# lipo.net
KiCad netlist of a schematic drawn in EAGLE
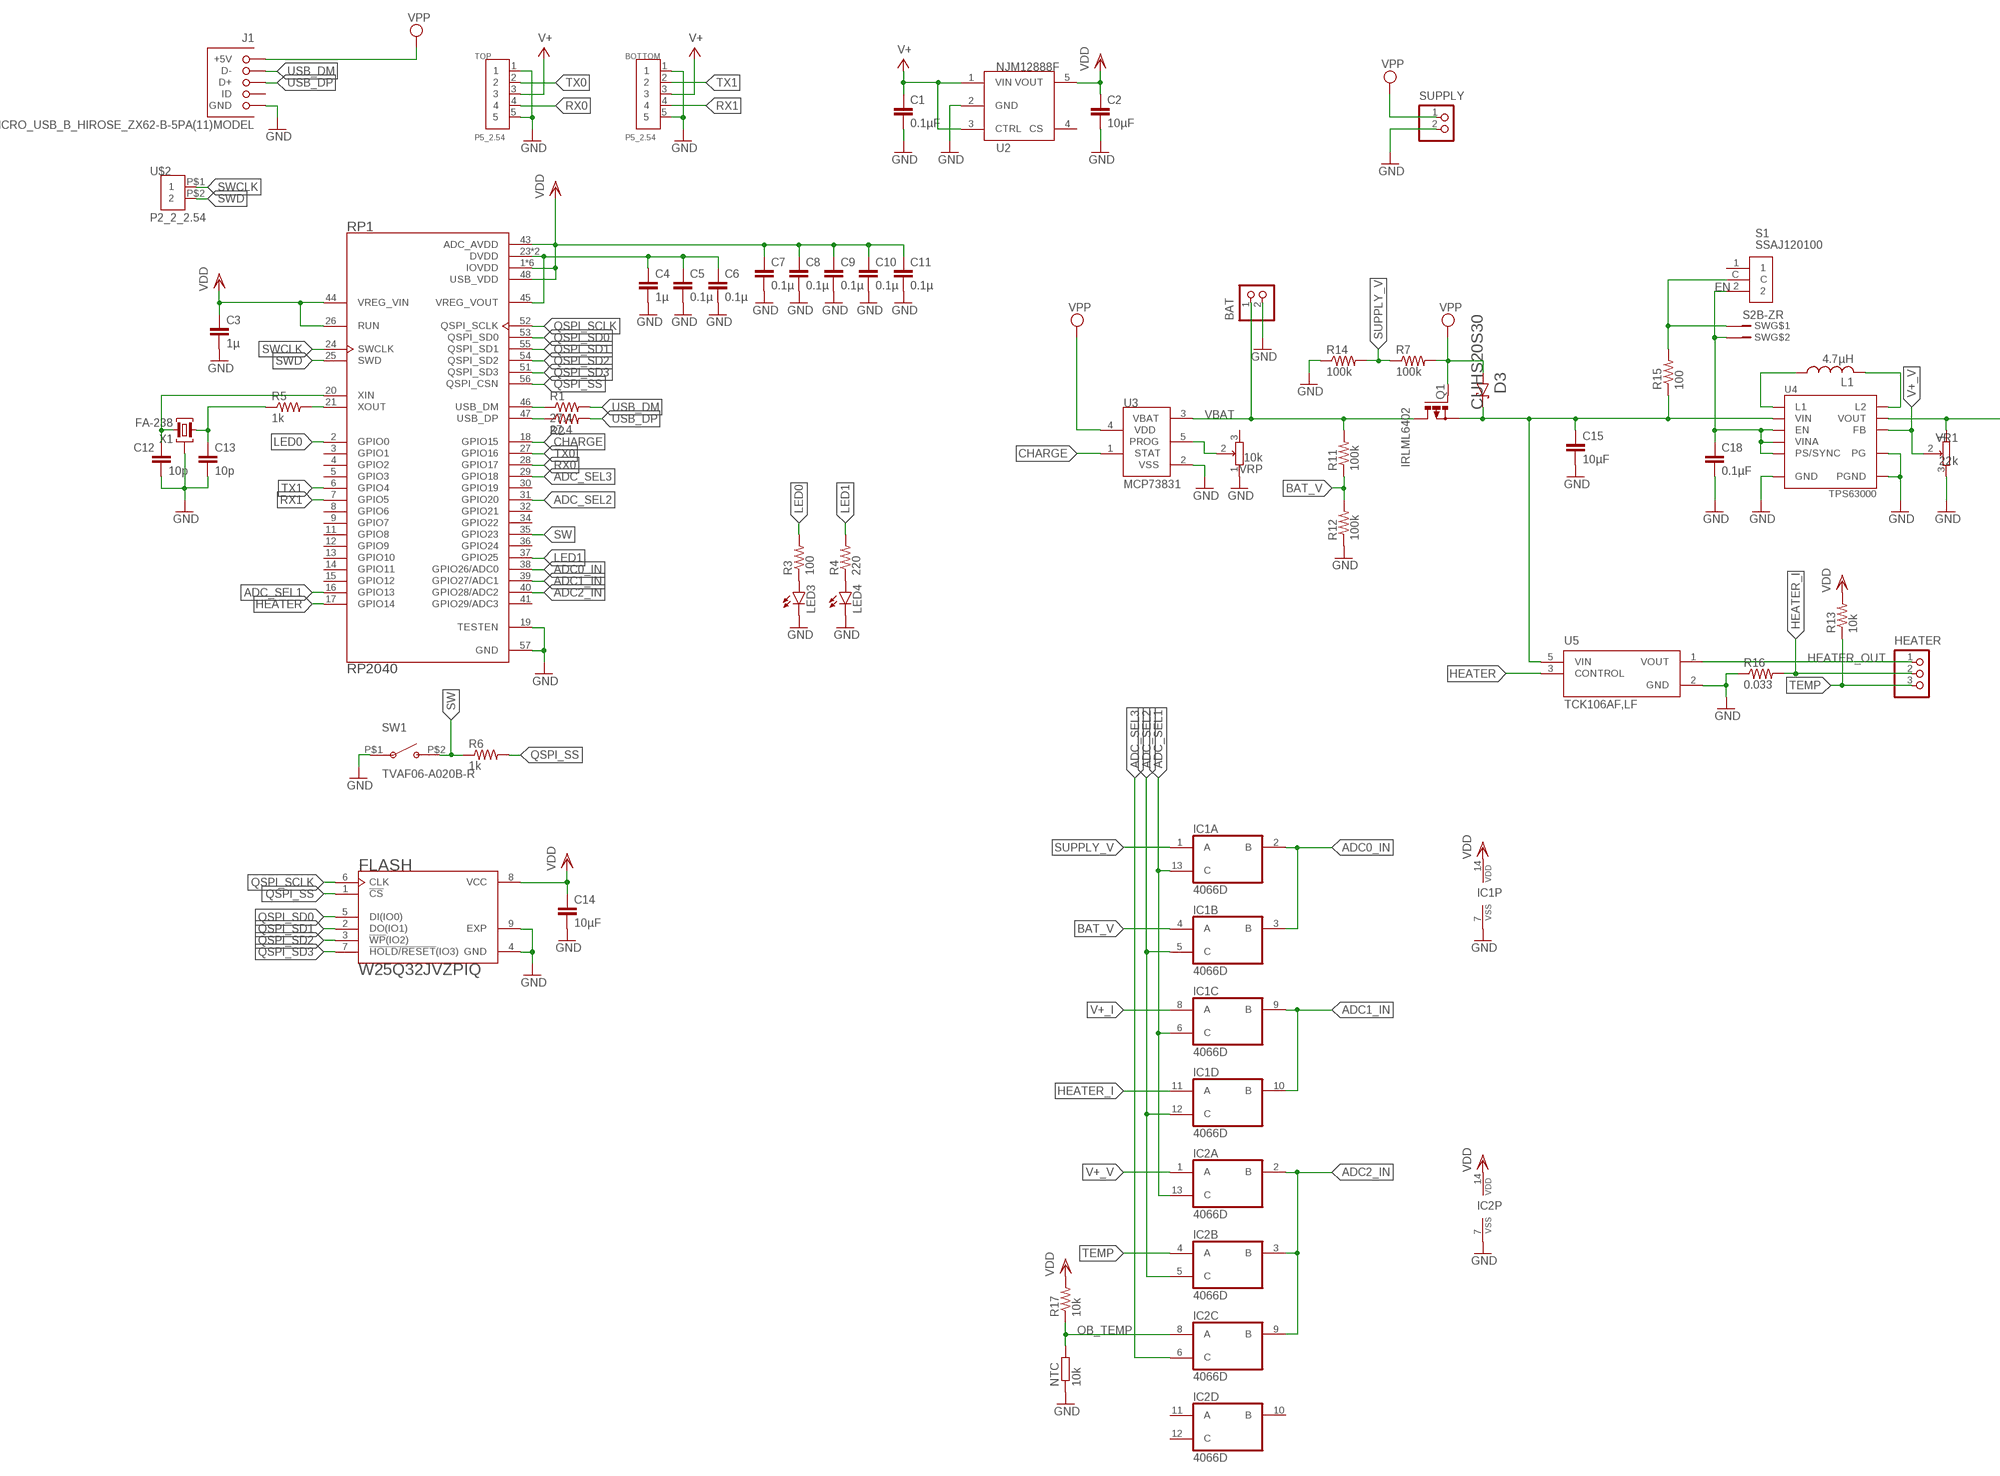
[diagram p0: schematic, sheet 1, part 1 of 2]
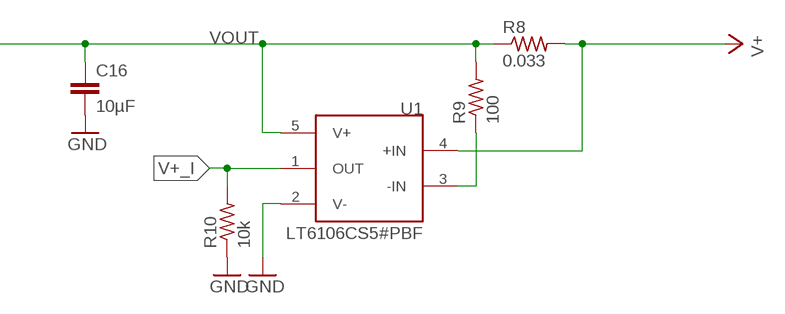
[diagram p1: schematic, sheet 1, part 2 of 2]

(export (version "E")
  (design (tool "Eeschema 10.0.6"))
  (components
    (comp (ref "BAT")
      (value "S2B-PH-K-S")
      (footprint "eagle-import:S2B-PH-K-S")
      (libsource (lib "eagle-import") (part "S2B-PH-K-S"))
    )
    (comp (ref "BOTTOM")
      (value "P5_2.54")
      (footprint "eagle-import:P5_2.54")
      (libsource (lib "eagle-import") (part "P5_2.54"))
    )
    (comp (ref "C1")
      (value "0.1µF")
      (footprint "eagle-import:C0402")
      (libsource (lib "eagle-import") (part "C-EUC0402"))
    )
    (comp (ref "C2")
      (value "10µF")
      (footprint "eagle-import:C0402")
      (libsource (lib "eagle-import") (part "C-EUC0402"))
    )
    (comp (ref "C3")
      (value "1µ")
      (footprint "eagle-import:C0402")
      (libsource (lib "eagle-import") (part "C-EUC0402"))
    )
    (comp (ref "C4")
      (value "1µ")
      (footprint "eagle-import:C0402")
      (libsource (lib "eagle-import") (part "C-EUC0402"))
    )
    (comp (ref "C5")
      (value "0.1µ")
      (footprint "eagle-import:C0402")
      (libsource (lib "eagle-import") (part "C-EUC0402"))
    )
    (comp (ref "C6")
      (value "0.1µ")
      (footprint "eagle-import:C0402")
      (libsource (lib "eagle-import") (part "C-EUC0402"))
    )
    (comp (ref "C7")
      (value "0.1µ")
      (footprint "eagle-import:C0402")
      (libsource (lib "eagle-import") (part "C-EUC0402"))
    )
    (comp (ref "C8")
      (value "0.1µ")
      (footprint "eagle-import:C0402")
      (libsource (lib "eagle-import") (part "C-EUC0402"))
    )
    (comp (ref "C9")
      (value "0.1µ")
      (footprint "eagle-import:C0402")
      (libsource (lib "eagle-import") (part "C-EUC0402"))
    )
    (comp (ref "C10")
      (value "0.1µ")
      (footprint "eagle-import:C0402")
      (libsource (lib "eagle-import") (part "C-EUC0402"))
    )
    (comp (ref "C11")
      (value "0.1µ")
      (footprint "eagle-import:C0402")
      (libsource (lib "eagle-import") (part "C-EUC0402"))
    )
    (comp (ref "C12")
      (value "10p")
      (footprint "eagle-import:C0402")
      (libsource (lib "eagle-import") (part "C-EUC0402"))
    )
    (comp (ref "C13")
      (value "10p")
      (footprint "eagle-import:C0402")
      (libsource (lib "eagle-import") (part "C-EUC0402"))
    )
    (comp (ref "C14")
      (value "10µF")
      (footprint "eagle-import:C0402")
      (libsource (lib "eagle-import") (part "C-EUC0402"))
    )
    (comp (ref "C15")
      (value "10µF")
      (footprint "eagle-import:C0402")
      (libsource (lib "eagle-import") (part "C-EUC0402"))
    )
    (comp (ref "C16")
      (value "10µF")
      (footprint "eagle-import:C0402")
      (libsource (lib "eagle-import") (part "C-EUC0402"))
    )
    (comp (ref "C18")
      (value "0.1µF")
      (footprint "eagle-import:C0402")
      (libsource (lib "eagle-import") (part "C-EUC0402"))
    )
    (comp (ref "D3")
      (value "CUHS20S30")
      (footprint "eagle-import:CUHS20S30")
      (libsource (lib "eagle-import") (part "CUHS20S30"))
    )
    (comp (ref "FLASH")
      (value "W25Q32JVZPIQ")
      (footprint "eagle-import:SON127P600X500X80-9N")
      (fields (field (name "MF") "Winbond"))
      (libsource (lib "eagle-import") (part "W25Q32JVZPIQ"))
    )
    (comp (ref "HEATER")
      (value "S3B-PH-K-S")
      (footprint "eagle-import:S3B-PH-K-S")
      (libsource (lib "eagle-import") (part "S3B-PH-K-S"))
    )
    (comp (ref "IC1")
      (value "4066D")
      (footprint "eagle-import:SO14")
      (libsource (lib "eagle-import") (part "4066D"))
    )
    (comp (ref "IC2")
      (value "4066D")
      (footprint "eagle-import:SO14")
      (libsource (lib "eagle-import") (part "4066D"))
    )
    (comp (ref "J1")
      (value "MICRO_USB_B_HIROSE_ZX62-B-5PA(11)MODEL")
      (footprint "eagle-import:GHI-CONNECTORS_10118192-0001LF(MICRO-USB-B-AMPHENOL-FCI)")
      (libsource (lib "eagle-import") (part "MICRO_USB_B_HIROSE_ZX62-B-5PA(11)MODEL"))
    )
    (comp (ref "L1")
      (value "4.7µH")
      (footprint "eagle-import:L3225M")
      (libsource (lib "eagle-import") (part "L-USL3225M"))
    )
    (comp (ref "LED3")
      (value "LEDCHIPLED_0603")
      (footprint "eagle-import:CHIPLED_0603")
      (libsource (lib "eagle-import") (part "LEDCHIPLED_0603"))
    )
    (comp (ref "LED4")
      (value "LEDCHIPLED_0603")
      (footprint "eagle-import:CHIPLED_0603")
      (libsource (lib "eagle-import") (part "LEDCHIPLED_0603"))
    )
    (comp (ref "NTC")
      (value "10k")
      (footprint "eagle-import:R0603")
      (libsource (lib "eagle-import") (part "R-EU_R0603"))
    )
    (comp (ref "Q1")
      (value "IRLML6402")
      (footprint "eagle-import:SOT-23")
      (libsource (lib "eagle-import") (part "IRLML6402"))
    )
    (comp (ref "R1")
      (value "27.4")
      (footprint "eagle-import:R0402")
      (libsource (lib "eagle-import") (part "R-US_R0402"))
    )
    (comp (ref "R2")
      (value "27.4")
      (footprint "eagle-import:R0402")
      (libsource (lib "eagle-import") (part "R-US_R0402"))
    )
    (comp (ref "R3")
      (value "100")
      (footprint "eagle-import:R0402")
      (libsource (lib "eagle-import") (part "R-US_R0402"))
    )
    (comp (ref "R4")
      (value "220")
      (footprint "eagle-import:R0402")
      (libsource (lib "eagle-import") (part "R-US_R0402"))
    )
    (comp (ref "R5")
      (value "1k")
      (footprint "eagle-import:R0402")
      (libsource (lib "eagle-import") (part "R-US_R0402"))
    )
    (comp (ref "R6")
      (value "1k")
      (footprint "eagle-import:R0402")
      (libsource (lib "eagle-import") (part "R-US_R0402"))
    )
    (comp (ref "R7")
      (value "100k")
      (footprint "eagle-import:R0402")
      (libsource (lib "eagle-import") (part "R-US_R0402"))
    )
    (comp (ref "R8")
      (value "0.033")
      (footprint "eagle-import:R0603")
      (libsource (lib "eagle-import") (part "R-US_R0603"))
    )
    (comp (ref "R9")
      (value "100")
      (footprint "eagle-import:R0402")
      (libsource (lib "eagle-import") (part "R-US_R0402"))
    )
    (comp (ref "R10")
      (value "10k")
      (footprint "eagle-import:R0402")
      (libsource (lib "eagle-import") (part "R-US_R0402"))
    )
    (comp (ref "R11")
      (value "100k")
      (footprint "eagle-import:R0402")
      (libsource (lib "eagle-import") (part "R-US_R0402"))
    )
    (comp (ref "R12")
      (value "100k")
      (footprint "eagle-import:R0402")
      (libsource (lib "eagle-import") (part "R-US_R0402"))
    )
    (comp (ref "R13")
      (value "10k")
      (footprint "eagle-import:R0402")
      (libsource (lib "eagle-import") (part "R-US_R0402"))
    )
    (comp (ref "R14")
      (value "100k")
      (footprint "eagle-import:R0402")
      (libsource (lib "eagle-import") (part "R-US_R0402"))
    )
    (comp (ref "R15")
      (value "100")
      (footprint "eagle-import:R0402")
      (libsource (lib "eagle-import") (part "R-US_R0402"))
    )
    (comp (ref "R16")
      (value "0.033")
      (footprint "eagle-import:R0603")
      (libsource (lib "eagle-import") (part "R-US_R0603"))
    )
    (comp (ref "R17")
      (value "10k")
      (footprint "eagle-import:R0402")
      (libsource (lib "eagle-import") (part "R-US_R0402"))
    )
    (comp (ref "RP1")
      (value "RP2040")
      (footprint "eagle-import:QFN40P700X700X90-57N")
      (fields (field (name "MF") "Raspberry Pi"))
      (libsource (lib "eagle-import") (part "RP2040"))
    )
    (comp (ref "S1")
      (value "SSAJ120100")
      (footprint "eagle-import:SSAJ120100")
      (fields (field (name "MOUSER_PART_NUMBER") "688-SSAJ120100") (field (name "RS_PART_NUMBER") "1238892"))
      (libsource (lib "eagle-import") (part "SSAJ120100"))
    )
    (comp (ref "SUPPLY")
      (value "S2B-PH-K-S")
      (footprint "eagle-import:S2B-PH-K-S")
      (libsource (lib "eagle-import") (part "S2B-PH-K-S"))
    )
    (comp (ref "SW")
      (value "S2B-ZR")
      (footprint "eagle-import:S2B-ZR")
      (libsource (lib "eagle-import") (part "S2B-ZR"))
    )
    (comp (ref "SW1")
      (value "TVAF06-A020B-R")
      (footprint "eagle-import:TVAF06-A020B-R")
      (libsource (lib "eagle-import") (part "TVAF06-A020B-R"))
    )
    (comp (ref "TOP")
      (value "P5_2.54")
      (footprint "eagle-import:P5_2.54")
      (libsource (lib "eagle-import") (part "P5_2.54"))
    )
    (comp (ref "U$2")
      (value "P2_2_2.54")
      (footprint "eagle-import:P2_2.54")
      (libsource (lib "eagle-import") (part "P2_2_2.54"))
    )
    (comp (ref "U1")
      (value "LT6106CS5#PBF")
      (footprint "eagle-import:SOT95P280X100-5N_LT6106CS5#PBF")
      (fields (field (name "MF") "Linear Technology"))
      (libsource (lib "eagle-import") (part "LT6106CS5#PBF"))
    )
    (comp (ref "U2")
      (value "NJM12888F")
      (footprint "eagle-import:SOT95P240X110-5N")
      (libsource (lib "eagle-import") (part "NJM12888F"))
    )
    (comp (ref "U3")
      (value "MCP73831")
      (footprint "eagle-import:SOT23-5L")
      (libsource (lib "eagle-import") (part "MCP73831"))
    )
    (comp (ref "U4")
      (value "TPS63000")
      (footprint "eagle-import:10-VFDFN")
      (fields (field (name "MF") "Texas Instruments"))
      (libsource (lib "eagle-import") (part "TPS63000"))
    )
    (comp (ref "U5")
      (value "TCK106AF,LF")
      (footprint "eagle-import:IC_TCK106AF,LF")
      (fields (field (name "MF") "Toshiba Semiconductor"))
      (libsource (lib "eagle-import") (part "TCK106AF,LF"))
    )
    (comp (ref "VR1")
      (value "22k")
      (footprint "eagle-import:PVZ3A")
      (libsource (lib "eagle-import") (part "PVZ3A"))
    )
    (comp (ref "VRP")
      (value "10k")
      (footprint "eagle-import:PVZ3A")
      (libsource (lib "eagle-import") (part "PVZ3A"))
    )
    (comp (ref "X1")
      (value "FA-238")
      (footprint "eagle-import:FA-238")
      (libsource (lib "eagle-import") (part "FA-238"))
    )
  )
  (nets
    (net (code "1") (name "/EN") (class "Default")
      (node (ref "C18") (pin "1") (pinfunction "1_1") (pintype "passive"))
      (node (ref "S1") (pin "2") (pinfunction "2_2") (pintype "bidirectional"))
      (node (ref "SW") (pin "2") (pinfunction "1_2") (pintype "passive"))
      (node (ref "U4") (pin "6") (pinfunction "EN_6") (pintype "bidirectional"))
      (node (ref "U4") (pin "7") (pinfunction "PS/SYNC_7") (pintype "input"))
      (node (ref "U4") (pin "8") (pinfunction "VINA_8") (pintype "power_in"))
    )
    (net (code "2") (name "/HEATER_OUT") (class "Default")
      (node (ref "HEATER") (pin "1") (pinfunction "1_1") (pintype "passive"))
      (node (ref "U5") (pin "1") (pinfunction "VOUT_1") (pintype "output"))
    )
    (net (code "3") (name "/OB_TEMP") (class "Default")
      (node (ref "IC2") (pin "8") (pinfunction "A_8") (pintype "tri_state"))
      (node (ref "NTC") (pin "2") (pinfunction "2_2") (pintype "passive"))
      (node (ref "R17") (pin "1") (pinfunction "1_1") (pintype "passive"))
    )
    (net (code "4") (name "/VBAT") (class "Default")
      (node (ref "BAT") (pin "1") (pinfunction "1_1") (pintype "passive"))
      (node (ref "Q1") (pin "P3") (pinfunction "D_P3") (pintype "passive"))
      (node (ref "R11") (pin "2") (pinfunction "2_2") (pintype "passive"))
      (node (ref "U3") (pin "3") (pinfunction "VBAT_3") (pintype "bidirectional"))
    )
    (net (code "5") (name "/VOUT") (class "Default")
      (node (ref "C16") (pin "1") (pinfunction "1_1") (pintype "passive"))
      (node (ref "R8") (pin "1") (pinfunction "1_1") (pintype "passive"))
      (node (ref "R9") (pin "2") (pinfunction "2_2") (pintype "passive"))
      (node (ref "U1") (pin "5") (pinfunction "V+_5") (pintype "power_in"))
      (node (ref "U4") (pin "1") (pinfunction "VOUT_1") (pintype "power_in"))
      (node (ref "VR1") (pin "1") (pinfunction "1_1") (pintype "bidirectional"))
    )
    (net (code "6") (name "ADC0_IN") (class "Default")
      (node (ref "IC1") (pin "2") (pinfunction "B_2") (pintype "tri_state"))
      (node (ref "IC1") (pin "3") (pinfunction "B_3") (pintype "tri_state"))
      (node (ref "RP1") (pin "38") (pinfunction "GPIO26/ADC0_38") (pintype "bidirectional"))
    )
    (net (code "7") (name "ADC1_IN") (class "Default")
      (node (ref "IC1") (pin "10") (pinfunction "B_10") (pintype "tri_state"))
      (node (ref "IC1") (pin "9") (pinfunction "B_9") (pintype "tri_state"))
      (node (ref "RP1") (pin "39") (pinfunction "GPIO27/ADC1_39") (pintype "bidirectional"))
    )
    (net (code "8") (name "ADC2_IN") (class "Default")
      (node (ref "IC2") (pin "2") (pinfunction "B_2") (pintype "tri_state"))
      (node (ref "IC2") (pin "3") (pinfunction "B_3") (pintype "tri_state"))
      (node (ref "IC2") (pin "9") (pinfunction "B_9") (pintype "tri_state"))
      (node (ref "RP1") (pin "40") (pinfunction "GPIO28/ADC2_40") (pintype "bidirectional"))
    )
    (net (code "9") (name "ADC_SEL1") (class "Default")
      (node (ref "IC1") (pin "13") (pinfunction "C_13") (pintype "input"))
      (node (ref "IC1") (pin "6") (pinfunction "C_6") (pintype "input"))
      (node (ref "IC2") (pin "13") (pinfunction "C_13") (pintype "input"))
      (node (ref "RP1") (pin "16") (pinfunction "GPIO13_16") (pintype "bidirectional"))
    )
    (net (code "10") (name "ADC_SEL2") (class "Default")
      (node (ref "IC1") (pin "12") (pinfunction "C_12") (pintype "input"))
      (node (ref "IC1") (pin "5") (pinfunction "C_5") (pintype "input"))
      (node (ref "IC2") (pin "5") (pinfunction "C_5") (pintype "input"))
      (node (ref "RP1") (pin "31") (pinfunction "GPIO20_31") (pintype "bidirectional"))
    )
    (net (code "11") (name "ADC_SEL3") (class "Default")
      (node (ref "IC2") (pin "6") (pinfunction "C_6") (pintype "input"))
      (node (ref "RP1") (pin "29") (pinfunction "GPIO18_29") (pintype "bidirectional"))
    )
    (net (code "12") (name "BAT_V") (class "Default")
      (node (ref "IC1") (pin "4") (pinfunction "A_4") (pintype "tri_state"))
      (node (ref "R11") (pin "1") (pinfunction "1_1") (pintype "passive"))
      (node (ref "R12") (pin "2") (pinfunction "2_2") (pintype "passive"))
    )
    (net (code "13") (name "CHARGE") (class "Default")
      (node (ref "RP1") (pin "18") (pinfunction "GPIO15_18") (pintype "bidirectional"))
      (node (ref "U3") (pin "1") (pinfunction "STAT_1") (pintype "bidirectional"))
    )
    (net (code "14") (name "GND") (class "Default")
      (node (ref "BAT") (pin "2") (pinfunction "2_2") (pintype "passive"))
      (node (ref "BOTTOM") (pin "1") (pinfunction "1_1") (pintype "bidirectional"))
      (node (ref "BOTTOM") (pin "5") (pinfunction "5_5") (pintype "bidirectional"))
      (node (ref "C1") (pin "2") (pinfunction "2_2") (pintype "passive"))
      (node (ref "C10") (pin "2") (pinfunction "2_2") (pintype "passive"))
      (node (ref "C11") (pin "2") (pinfunction "2_2") (pintype "passive"))
      (node (ref "C12") (pin "2") (pinfunction "2_2") (pintype "passive"))
      (node (ref "C13") (pin "2") (pinfunction "2_2") (pintype "passive"))
      (node (ref "C14") (pin "2") (pinfunction "2_2") (pintype "passive"))
      (node (ref "C15") (pin "2") (pinfunction "2_2") (pintype "passive"))
      (node (ref "C16") (pin "2") (pinfunction "2_2") (pintype "passive"))
      (node (ref "C18") (pin "2") (pinfunction "2_2") (pintype "passive"))
      (node (ref "C2") (pin "2") (pinfunction "2_2") (pintype "passive"))
      (node (ref "C3") (pin "2") (pinfunction "2_2") (pintype "passive"))
      (node (ref "C4") (pin "2") (pinfunction "2_2") (pintype "passive"))
      (node (ref "C5") (pin "2") (pinfunction "2_2") (pintype "passive"))
      (node (ref "C6") (pin "2") (pinfunction "2_2") (pintype "passive"))
      (node (ref "C7") (pin "2") (pinfunction "2_2") (pintype "passive"))
      (node (ref "C8") (pin "2") (pinfunction "2_2") (pintype "passive"))
      (node (ref "C9") (pin "2") (pinfunction "2_2") (pintype "passive"))
      (node (ref "FLASH") (pin "4") (pinfunction "GND_4") (pintype "power_in"))
      (node (ref "FLASH") (pin "9") (pinfunction "EXP_9") (pintype "passive"))
      (node (ref "IC1") (pin "7") (pinfunction "VSS_7") (pintype "power_in"))
      (node (ref "IC2") (pin "7") (pinfunction "VSS_7") (pintype "power_in"))
      (node (ref "J1") (pin "CGND1") (pinfunction "GND_CGND1") (pintype "bidirectional"))
      (node (ref "J1") (pin "CGND2") (pinfunction "GND_CGND2") (pintype "bidirectional"))
      (node (ref "J1") (pin "CGND3") (pinfunction "GND_CGND3") (pintype "bidirectional"))
      (node (ref "J1") (pin "CGND4") (pinfunction "GND_CGND4") (pintype "bidirectional"))
      (node (ref "J1") (pin "CGND5") (pinfunction "GND_CGND5") (pintype "bidirectional"))
      (node (ref "J1") (pin "CGND6") (pinfunction "GND_CGND6") (pintype "bidirectional"))
      (node (ref "J1") (pin "GND") (pinfunction "GND_GND") (pintype "bidirectional"))
      (node (ref "LED3") (pin "C") (pinfunction "C_C") (pintype "passive"))
      (node (ref "LED4") (pin "C") (pinfunction "C_C") (pintype "passive"))
      (node (ref "NTC") (pin "1") (pinfunction "1_1") (pintype "passive"))
      (node (ref "R10") (pin "1") (pinfunction "1_1") (pintype "passive"))
      (node (ref "R12") (pin "1") (pinfunction "1_1") (pintype "passive"))
      (node (ref "R14") (pin "1") (pinfunction "1_1") (pintype "passive"))
      (node (ref "R16") (pin "1") (pinfunction "1_1") (pintype "passive"))
      (node (ref "RP1") (pin "19") (pinfunction "TESTEN_19") (pintype "passive"))
      (node (ref "RP1") (pin "57") (pinfunction "GND_57") (pintype "power_in"))
      (node (ref "SUPPLY") (pin "2") (pinfunction "2_2") (pintype "passive"))
      (node (ref "SW1") (pin "P$1") (pinfunction "A_P$1") (pintype "bidirectional"))
      (node (ref "TOP") (pin "1") (pinfunction "1_1") (pintype "bidirectional"))
      (node (ref "TOP") (pin "5") (pinfunction "5_5") (pintype "bidirectional"))
      (node (ref "U1") (pin "2") (pinfunction "V-_2") (pintype "power_in"))
      (node (ref "U2") (pin "2") (pinfunction "GND_2") (pintype "power_in"))
      (node (ref "U3") (pin "2") (pinfunction "VSS_2") (pintype "bidirectional"))
      (node (ref "U4") (pin "3") (pinfunction "PGND_3") (pintype "power_in"))
      (node (ref "U4") (pin "9") (pinfunction "GND_9") (pintype "power_in"))
      (node (ref "U4") (pin "P$1") (pinfunction "PG_P$1") (pintype "power_in"))
      (node (ref "U4") (pin "P$2") (pinfunction "PG_P$2") (pintype "power_in"))
      (node (ref "U4") (pin "P$3") (pinfunction "PG_P$3") (pintype "power_in"))
      (node (ref "U4") (pin "P$4") (pinfunction "PG_P$4") (pintype "power_in"))
      (node (ref "U4") (pin "P$5") (pinfunction "PG_P$5") (pintype "power_in"))
      (node (ref "U5") (pin "2") (pinfunction "GND_2") (pintype "power_in"))
      (node (ref "VR1") (pin "3") (pinfunction "3_3") (pintype "bidirectional"))
      (node (ref "VRP") (pin "1") (pinfunction "1_1") (pintype "bidirectional"))
      (node (ref "X1") (pin "2") (pinfunction "G_2") (pintype "passive"))
      (node (ref "X1") (pin "4") (pinfunction "G_4") (pintype "passive"))
    )
    (net (code "15") (name "HEATER") (class "Default")
      (node (ref "RP1") (pin "17") (pinfunction "GPIO14_17") (pintype "bidirectional"))
      (node (ref "U5") (pin "3") (pinfunction "CONTROL_3") (pintype "input"))
    )
    (net (code "16") (name "HEATER_I") (class "Default")
      (node (ref "HEATER") (pin "2") (pinfunction "2_2") (pintype "passive"))
      (node (ref "IC1") (pin "11") (pinfunction "A_11") (pintype "tri_state"))
      (node (ref "R16") (pin "2") (pinfunction "2_2") (pintype "passive"))
    )
    (net (code "17") (name "LED0") (class "Default")
      (node (ref "R3") (pin "2") (pinfunction "2_2") (pintype "passive"))
      (node (ref "RP1") (pin "2") (pinfunction "GPIO0_2") (pintype "bidirectional"))
    )
    (net (code "18") (name "LED1") (class "Default")
      (node (ref "R4") (pin "2") (pinfunction "2_2") (pintype "passive"))
      (node (ref "RP1") (pin "37") (pinfunction "GPIO25_37") (pintype "bidirectional"))
    )
    (net (code "19") (name "Net-(C13-Pad1)") (class "Default")
      (node (ref "C13") (pin "1") (pinfunction "1_1") (pintype "passive"))
      (node (ref "R5") (pin "1") (pinfunction "1_1") (pintype "passive"))
      (node (ref "X1") (pin "1") (pinfunction "1_1") (pintype "passive"))
    )
    (net (code "20") (name "Net-(LED3-PadA)") (class "Default")
      (node (ref "LED3") (pin "A") (pinfunction "A_A") (pintype "passive"))
      (node (ref "R3") (pin "1") (pinfunction "1_1") (pintype "passive"))
    )
    (net (code "21") (name "Net-(LED4-PadA)") (class "Default")
      (node (ref "LED4") (pin "A") (pinfunction "A_A") (pintype "passive"))
      (node (ref "R4") (pin "1") (pinfunction "1_1") (pintype "passive"))
    )
    (net (code "22") (name "Net-(Q1-S)") (class "Default")
      (node (ref "C15") (pin "1") (pinfunction "1_1") (pintype "passive"))
      (node (ref "D3") (pin "C") (pinfunction "C_C") (pintype "bidirectional"))
      (node (ref "Q1") (pin "P2") (pinfunction "S_P2") (pintype "passive"))
      (node (ref "R15") (pin "1") (pinfunction "1_1") (pintype "passive"))
      (node (ref "U4") (pin "5") (pinfunction "VIN_5") (pintype "power_in"))
      (node (ref "U5") (pin "5") (pinfunction "VIN_5") (pintype "input"))
    )
    (net (code "23") (name "Net-(R15-Pad2)") (class "Default")
      (node (ref "R15") (pin "2") (pinfunction "2_2") (pintype "passive"))
      (node (ref "S1") (pin "C") (pinfunction "C_C") (pintype "bidirectional"))
      (node (ref "SW") (pin "1") (pinfunction "1_1") (pintype "passive"))
    )
    (net (code "24") (name "Net-(RP1-USB_DM)") (class "Default")
      (node (ref "R1") (pin "1") (pinfunction "1_1") (pintype "passive"))
      (node (ref "RP1") (pin "46") (pinfunction "USB_DM_46") (pintype "bidirectional"))
    )
    (net (code "25") (name "Net-(RP1-USB_DP)") (class "Default")
      (node (ref "R2") (pin "1") (pinfunction "1_1") (pintype "passive"))
      (node (ref "RP1") (pin "47") (pinfunction "USB_DP_47") (pintype "bidirectional"))
    )
    (net (code "26") (name "Net-(RP1-VREG_VOUT)") (class "Default")
      (node (ref "C4") (pin "1") (pinfunction "1_1") (pintype "passive"))
      (node (ref "C5") (pin "1") (pinfunction "1_1") (pintype "passive"))
      (node (ref "C6") (pin "1") (pinfunction "1_1") (pintype "passive"))
      (node (ref "RP1") (pin "23") (pinfunction "DVDD_23") (pintype "power_in"))
      (node (ref "RP1") (pin "45") (pinfunction "VREG_VOUT_45") (pintype "output"))
      (node (ref "RP1") (pin "50") (pinfunction "DVDD_50") (pintype "power_in"))
    )
    (net (code "27") (name "Net-(RP1-XIN)") (class "Default")
      (node (ref "C12") (pin "1") (pinfunction "1_1") (pintype "passive"))
      (node (ref "RP1") (pin "20") (pinfunction "XIN_20") (pintype "input"))
      (node (ref "X1") (pin "3") (pinfunction "2_3") (pintype "passive"))
    )
    (net (code "28") (name "Net-(RP1-XOUT)") (class "Default")
      (node (ref "R5") (pin "2") (pinfunction "2_2") (pintype "passive"))
      (node (ref "RP1") (pin "21") (pinfunction "XOUT_21") (pintype "output"))
    )
    (net (code "29") (name "Net-(U1--IN)") (class "Default")
      (node (ref "R9") (pin "1") (pinfunction "1_1") (pintype "passive"))
      (node (ref "U1") (pin "3") (pinfunction "-IN_3") (pintype "input"))
    )
    (net (code "30") (name "Net-(U3-PROG)") (class "Default")
      (node (ref "U3") (pin "5") (pinfunction "PROG_5") (pintype "bidirectional"))
      (node (ref "VRP") (pin "2") (pinfunction "2_2") (pintype "bidirectional"))
    )
    (net (code "31") (name "Net-(U4-L1)") (class "Default")
      (node (ref "L1") (pin "1") (pinfunction "1_1") (pintype "passive"))
      (node (ref "U4") (pin "4") (pinfunction "L1_4") (pintype "passive"))
    )
    (net (code "32") (name "Net-(U4-L2)") (class "Default")
      (node (ref "L1") (pin "2") (pinfunction "2_2") (pintype "passive"))
      (node (ref "U4") (pin "2") (pinfunction "L2_2") (pintype "passive"))
    )
    (net (code "33") (name "QSPI_SCLK") (class "Default")
      (node (ref "FLASH") (pin "6") (pinfunction "CLK_6") (pintype "input"))
      (node (ref "RP1") (pin "52") (pinfunction "QSPI_SCLK_52") (pintype "bidirectional"))
    )
    (net (code "34") (name "QSPI_SD0") (class "Default")
      (node (ref "FLASH") (pin "5") (pinfunction "DI(IO0)_5") (pintype "bidirectional"))
      (node (ref "RP1") (pin "53") (pinfunction "QSPI_SD0_53") (pintype "bidirectional"))
    )
    (net (code "35") (name "QSPI_SD1") (class "Default")
      (node (ref "FLASH") (pin "2") (pinfunction "DO(IO1)_2") (pintype "bidirectional"))
      (node (ref "RP1") (pin "55") (pinfunction "QSPI_SD1_55") (pintype "bidirectional"))
    )
    (net (code "36") (name "QSPI_SD2") (class "Default")
      (node (ref "FLASH") (pin "3") (pinfunction "~{WP}(IO2)_3") (pintype "bidirectional"))
      (node (ref "RP1") (pin "54") (pinfunction "QSPI_SD2_54") (pintype "bidirectional"))
    )
    (net (code "37") (name "QSPI_SD3") (class "Default")
      (node (ref "FLASH") (pin "7") (pinfunction "~{HOLD/RESET}(IO3)_7") (pintype "bidirectional"))
      (node (ref "RP1") (pin "51") (pinfunction "QSPI_SD3_51") (pintype "bidirectional"))
    )
    (net (code "38") (name "QSPI_SS") (class "Default")
      (node (ref "FLASH") (pin "1") (pinfunction "~{CS}_1") (pintype "input"))
      (node (ref "R6") (pin "2") (pinfunction "2_2") (pintype "passive"))
      (node (ref "RP1") (pin "56") (pinfunction "QSPI_CSN_56") (pintype "bidirectional"))
    )
    (net (code "39") (name "RX0") (class "Default")
      (node (ref "RP1") (pin "28") (pinfunction "GPIO17_28") (pintype "bidirectional"))
      (node (ref "TOP") (pin "4") (pinfunction "4_4") (pintype "bidirectional"))
    )
    (net (code "40") (name "RX1") (class "Default")
      (node (ref "BOTTOM") (pin "4") (pinfunction "4_4") (pintype "bidirectional"))
      (node (ref "RP1") (pin "7") (pinfunction "GPIO5_7") (pintype "bidirectional"))
    )
    (net (code "41") (name "SUPPLY_V") (class "Default")
      (node (ref "IC1") (pin "1") (pinfunction "A_1") (pintype "tri_state"))
      (node (ref "R14") (pin "2") (pinfunction "2_2") (pintype "passive"))
      (node (ref "R7") (pin "1") (pinfunction "1_1") (pintype "passive"))
    )
    (net (code "42") (name "SW") (class "Default")
      (node (ref "R6") (pin "1") (pinfunction "1_1") (pintype "passive"))
      (node (ref "RP1") (pin "35") (pinfunction "GPIO23_35") (pintype "bidirectional"))
      (node (ref "SW1") (pin "P$2") (pinfunction "B_P$2") (pintype "bidirectional"))
    )
    (net (code "43") (name "SWCLK") (class "Default")
      (node (ref "RP1") (pin "24") (pinfunction "SWCLK_24") (pintype "input"))
      (node (ref "U$2") (pin "P$1") (pinfunction "1_P$1") (pintype "bidirectional"))
    )
    (net (code "44") (name "SWD") (class "Default")
      (node (ref "RP1") (pin "25") (pinfunction "SWD_25") (pintype "bidirectional"))
      (node (ref "U$2") (pin "P$2") (pinfunction "2_P$2") (pintype "bidirectional"))
    )
    (net (code "45") (name "TEMP") (class "Default")
      (node (ref "HEATER") (pin "3") (pinfunction "3_3") (pintype "passive"))
      (node (ref "IC2") (pin "4") (pinfunction "A_4") (pintype "tri_state"))
      (node (ref "R13") (pin "1") (pinfunction "1_1") (pintype "passive"))
    )
    (net (code "46") (name "TX0") (class "Default")
      (node (ref "RP1") (pin "27") (pinfunction "GPIO16_27") (pintype "bidirectional"))
      (node (ref "TOP") (pin "2") (pinfunction "2_2") (pintype "bidirectional"))
    )
    (net (code "47") (name "TX1") (class "Default")
      (node (ref "BOTTOM") (pin "2") (pinfunction "2_2") (pintype "bidirectional"))
      (node (ref "RP1") (pin "6") (pinfunction "GPIO4_6") (pintype "bidirectional"))
    )
    (net (code "48") (name "USB_DM") (class "Default")
      (node (ref "J1") (pin "D-") (pinfunction "D-_D-") (pintype "bidirectional"))
      (node (ref "R1") (pin "2") (pinfunction "2_2") (pintype "passive"))
    )
    (net (code "49") (name "USB_DP") (class "Default")
      (node (ref "J1") (pin "D+") (pinfunction "D+_D+") (pintype "bidirectional"))
      (node (ref "R2") (pin "2") (pinfunction "2_2") (pintype "passive"))
    )
    (net (code "50") (name "V+") (class "Default")
      (node (ref "BOTTOM") (pin "3") (pinfunction "3_3") (pintype "bidirectional"))
      (node (ref "C1") (pin "1") (pinfunction "1_1") (pintype "passive"))
      (node (ref "R8") (pin "2") (pinfunction "2_2") (pintype "passive"))
      (node (ref "TOP") (pin "3") (pinfunction "3_3") (pintype "bidirectional"))
      (node (ref "U1") (pin "4") (pinfunction "+IN_4") (pintype "input"))
      (node (ref "U2") (pin "1") (pinfunction "VIN_1") (pintype "power_in"))
      (node (ref "U2") (pin "3") (pinfunction "CTRL_3") (pintype "input"))
    )
    (net (code "51") (name "V+_I") (class "Default")
      (node (ref "IC1") (pin "8") (pinfunction "A_8") (pintype "tri_state"))
      (node (ref "R10") (pin "2") (pinfunction "2_2") (pintype "passive"))
      (node (ref "U1") (pin "1") (pinfunction "OUT_1") (pintype "output"))
    )
    (net (code "52") (name "V+_V") (class "Default")
      (node (ref "IC2") (pin "1") (pinfunction "A_1") (pintype "tri_state"))
      (node (ref "U4") (pin "10") (pinfunction "FB_10") (pintype "input"))
      (node (ref "VR1") (pin "2") (pinfunction "2_2") (pintype "bidirectional"))
    )
    (net (code "53") (name "VDD") (class "Default")
      (node (ref "C10") (pin "1") (pinfunction "1_1") (pintype "passive"))
      (node (ref "C11") (pin "1") (pinfunction "1_1") (pintype "passive"))
      (node (ref "C14") (pin "1") (pinfunction "1_1") (pintype "passive"))
      (node (ref "C2") (pin "1") (pinfunction "1_1") (pintype "passive"))
      (node (ref "C3") (pin "1") (pinfunction "1_1") (pintype "passive"))
      (node (ref "C7") (pin "1") (pinfunction "1_1") (pintype "passive"))
      (node (ref "C8") (pin "1") (pinfunction "1_1") (pintype "passive"))
      (node (ref "C9") (pin "1") (pinfunction "1_1") (pintype "passive"))
      (node (ref "FLASH") (pin "8") (pinfunction "VCC_8") (pintype "power_in"))
      (node (ref "IC1") (pin "14") (pinfunction "VDD_14") (pintype "power_in"))
      (node (ref "IC2") (pin "14") (pinfunction "VDD_14") (pintype "power_in"))
      (node (ref "R13") (pin "2") (pinfunction "2_2") (pintype "passive"))
      (node (ref "R17") (pin "2") (pinfunction "2_2") (pintype "passive"))
      (node (ref "RP1") (pin "1") (pinfunction "IOVDD_1") (pintype "power_in"))
      (node (ref "RP1") (pin "10") (pinfunction "IOVDD_10") (pintype "power_in"))
      (node (ref "RP1") (pin "22") (pinfunction "IOVDD_22") (pintype "power_in"))
      (node (ref "RP1") (pin "26") (pinfunction "RUN_26") (pintype "input"))
      (node (ref "RP1") (pin "33") (pinfunction "IOVDD_33") (pintype "power_in"))
      (node (ref "RP1") (pin "42") (pinfunction "IOVDD_42") (pintype "power_in"))
      (node (ref "RP1") (pin "43") (pinfunction "ADC_AVDD_43") (pintype "power_in"))
      (node (ref "RP1") (pin "44") (pinfunction "VREG_VIN_44") (pintype "input"))
      (node (ref "RP1") (pin "48") (pinfunction "USB_VDD_48") (pintype "power_in"))
      (node (ref "RP1") (pin "49") (pinfunction "IOVDD_49") (pintype "power_in"))
      (node (ref "U2") (pin "5") (pinfunction "VOUT_5") (pintype "power_in"))
    )
    (net (code "54") (name "VPP") (class "Default")
      (node (ref "D3") (pin "A") (pinfunction "A_A") (pintype "bidirectional"))
      (node (ref "J1") (pin "VBUS") (pinfunction "+5V_VBUS") (pintype "bidirectional"))
      (node (ref "Q1") (pin "P1") (pinfunction "G_P1") (pintype "passive"))
      (node (ref "R7") (pin "2") (pinfunction "2_2") (pintype "passive"))
      (node (ref "SUPPLY") (pin "1") (pinfunction "1_1") (pintype "passive"))
      (node (ref "U3") (pin "4") (pinfunction "VDD_4") (pintype "bidirectional"))
    )
    (net (code "55") (name "unconnected-(IC2D-A-Pad11)") (class "Default")
      (node (ref "IC2") (pin "11") (pinfunction "A_11") (pintype "tri_state"))
    )
    (net (code "56") (name "unconnected-(IC2D-B-Pad10)") (class "Default")
      (node (ref "IC2") (pin "10") (pinfunction "B_10") (pintype "tri_state"))
    )
    (net (code "57") (name "unconnected-(IC2D-C-Pad12)") (class "Default")
      (node (ref "IC2") (pin "12") (pinfunction "C_12") (pintype "input"))
    )
    (net (code "58") (name "unconnected-(J1-PadID)") (class "Default")
      (node (ref "J1") (pin "ID") (pinfunction "ID_ID") (pintype "bidirectional"))
    )
    (net (code "59") (name "unconnected-(RP1-GPIO1-Pad3)") (class "Default")
      (node (ref "RP1") (pin "3") (pinfunction "GPIO1_3") (pintype "bidirectional"))
    )
    (net (code "60") (name "unconnected-(RP1-GPIO2-Pad4)") (class "Default")
      (node (ref "RP1") (pin "4") (pinfunction "GPIO2_4") (pintype "bidirectional"))
    )
    (net (code "61") (name "unconnected-(RP1-GPIO3-Pad5)") (class "Default")
      (node (ref "RP1") (pin "5") (pinfunction "GPIO3_5") (pintype "bidirectional"))
    )
    (net (code "62") (name "unconnected-(RP1-GPIO6-Pad8)") (class "Default")
      (node (ref "RP1") (pin "8") (pinfunction "GPIO6_8") (pintype "bidirectional"))
    )
    (net (code "63") (name "unconnected-(RP1-GPIO7-Pad9)") (class "Default")
      (node (ref "RP1") (pin "9") (pinfunction "GPIO7_9") (pintype "bidirectional"))
    )
    (net (code "64") (name "unconnected-(RP1-GPIO8-Pad11)") (class "Default")
      (node (ref "RP1") (pin "11") (pinfunction "GPIO8_11") (pintype "bidirectional"))
    )
    (net (code "65") (name "unconnected-(RP1-GPIO9-Pad12)") (class "Default")
      (node (ref "RP1") (pin "12") (pinfunction "GPIO9_12") (pintype "bidirectional"))
    )
    (net (code "66") (name "unconnected-(RP1-GPIO10-Pad13)") (class "Default")
      (node (ref "RP1") (pin "13") (pinfunction "GPIO10_13") (pintype "bidirectional"))
    )
    (net (code "67") (name "unconnected-(RP1-GPIO11-Pad14)") (class "Default")
      (node (ref "RP1") (pin "14") (pinfunction "GPIO11_14") (pintype "bidirectional"))
    )
    (net (code "68") (name "unconnected-(RP1-GPIO12-Pad15)") (class "Default")
      (node (ref "RP1") (pin "15") (pinfunction "GPIO12_15") (pintype "bidirectional"))
    )
    (net (code "69") (name "unconnected-(RP1-GPIO19-Pad30)") (class "Default")
      (node (ref "RP1") (pin "30") (pinfunction "GPIO19_30") (pintype "bidirectional"))
    )
    (net (code "70") (name "unconnected-(RP1-GPIO21-Pad32)") (class "Default")
      (node (ref "RP1") (pin "32") (pinfunction "GPIO21_32") (pintype "bidirectional"))
    )
    (net (code "71") (name "unconnected-(RP1-GPIO22-Pad34)") (class "Default")
      (node (ref "RP1") (pin "34") (pinfunction "GPIO22_34") (pintype "bidirectional"))
    )
    (net (code "72") (name "unconnected-(RP1-GPIO24-Pad36)") (class "Default")
      (node (ref "RP1") (pin "36") (pinfunction "GPIO24_36") (pintype "bidirectional"))
    )
    (net (code "73") (name "unconnected-(RP1-GPIO29{slash}ADC3-Pad41)") (class "Default")
      (node (ref "RP1") (pin "41") (pinfunction "GPIO29/ADC3_41") (pintype "bidirectional"))
    )
    (net (code "74") (name "unconnected-(S1-Pad1)") (class "Default")
      (node (ref "S1") (pin "1") (pinfunction "1_1") (pintype "bidirectional"))
    )
    (net (code "75") (name "unconnected-(U2-CS-Pad4)") (class "Default")
      (node (ref "U2") (pin "4") (pinfunction "CS_4") (pintype "input"))
    )
    (net (code "76") (name "unconnected-(VRP-Pad3)") (class "Default")
      (node (ref "VRP") (pin "3") (pinfunction "3_3") (pintype "bidirectional"))
    )
  )
)
